# 3xAttenuators.net
KiCad netlist of a schematic drawn in EAGLE
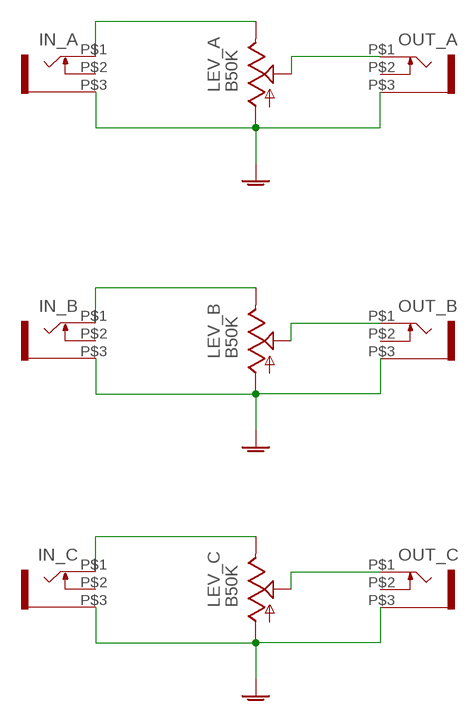
[diagram p0: schematic, sheet 1]

(export (version "E")
  (design (tool "Eeschema 10.0.6"))
  (components
    (comp (ref "IN_A")
      (value "THONKICONN_WQP-PJ301M-12_JACK")
      (footprint "eagle-import:THONKICONN_WQP-PJ301M-12_JACK")
      (libsource (lib "eagle-import") (part "THONKICONN_WQP-PJ301M-12_JACK"))
    )
    (comp (ref "IN_B")
      (value "THONKICONN_WQP-PJ301M-12_JACK")
      (footprint "eagle-import:THONKICONN_WQP-PJ301M-12_JACK")
      (libsource (lib "eagle-import") (part "THONKICONN_WQP-PJ301M-12_JACK"))
    )
    (comp (ref "IN_C")
      (value "THONKICONN_WQP-PJ301M-12_JACK")
      (footprint "eagle-import:THONKICONN_WQP-PJ301M-12_JACK")
      (libsource (lib "eagle-import") (part "THONKICONN_WQP-PJ301M-12_JACK"))
    )
    (comp (ref "LEV_A")
      (value "B50K")
      (footprint "eagle-import:MUSICTHINGMODULAR_9MM_SNAP-IN_POT")
      (libsource (lib "eagle-import") (part "MUSICTHINGMODULAR_9MM_SNAP-IN_POT_"))
    )
    (comp (ref "LEV_B")
      (value "B50K")
      (footprint "eagle-import:MUSICTHINGMODULAR_9MM_SNAP-IN_POT")
      (libsource (lib "eagle-import") (part "MUSICTHINGMODULAR_9MM_SNAP-IN_POT_"))
    )
    (comp (ref "LEV_C")
      (value "B50K")
      (footprint "eagle-import:MUSICTHINGMODULAR_9MM_SNAP-IN_POT")
      (libsource (lib "eagle-import") (part "MUSICTHINGMODULAR_9MM_SNAP-IN_POT_"))
    )
    (comp (ref "OUT_A")
      (value "THONKICONN_WQP-PJ301M-12_JACK")
      (footprint "eagle-import:THONKICONN_WQP-PJ301M-12_JACK")
      (libsource (lib "eagle-import") (part "THONKICONN_WQP-PJ301M-12_JACK"))
    )
    (comp (ref "OUT_B")
      (value "THONKICONN_WQP-PJ301M-12_JACK")
      (footprint "eagle-import:THONKICONN_WQP-PJ301M-12_JACK")
      (libsource (lib "eagle-import") (part "THONKICONN_WQP-PJ301M-12_JACK"))
    )
    (comp (ref "OUT_C")
      (value "THONKICONN_WQP-PJ301M-12_JACK")
      (footprint "eagle-import:THONKICONN_WQP-PJ301M-12_JACK")
      (libsource (lib "eagle-import") (part "THONKICONN_WQP-PJ301M-12_JACK"))
    )
  )
  (nets
    (net (code "1") (name "GNDA") (class "Default")
      (node (ref "IN_A") (pin "P$3") (pinfunction "1_P$3") (pintype "passive"))
      (node (ref "IN_B") (pin "P$3") (pinfunction "1_P$3") (pintype "passive"))
      (node (ref "IN_C") (pin "P$3") (pinfunction "1_P$3") (pintype "passive"))
      (node (ref "LEV_A") (pin "1") (pinfunction "A_1") (pintype "passive"))
      (node (ref "LEV_B") (pin "1") (pinfunction "A_1") (pintype "passive"))
      (node (ref "LEV_C") (pin "1") (pinfunction "A_1") (pintype "passive"))
      (node (ref "OUT_A") (pin "P$3") (pinfunction "1_P$3") (pintype "passive"))
      (node (ref "OUT_B") (pin "P$3") (pinfunction "1_P$3") (pintype "passive"))
      (node (ref "OUT_C") (pin "P$3") (pinfunction "1_P$3") (pintype "passive"))
    )
    (net (code "2") (name "Net-(IN_A-2)") (class "Default")
      (node (ref "IN_A") (pin "P$1") (pinfunction "2_P$1") (pintype "passive"))
      (node (ref "LEV_A") (pin "3") (pinfunction "E_3") (pintype "passive"))
    )
    (net (code "3") (name "Net-(IN_B-2)") (class "Default")
      (node (ref "IN_B") (pin "P$1") (pinfunction "2_P$1") (pintype "passive"))
      (node (ref "LEV_B") (pin "3") (pinfunction "E_3") (pintype "passive"))
    )
    (net (code "4") (name "Net-(IN_C-2)") (class "Default")
      (node (ref "IN_C") (pin "P$1") (pinfunction "2_P$1") (pintype "passive"))
      (node (ref "LEV_C") (pin "3") (pinfunction "E_3") (pintype "passive"))
    )
    (net (code "5") (name "Net-(LEV_A-S)") (class "Default")
      (node (ref "LEV_A") (pin "2") (pinfunction "S_2") (pintype "passive"))
      (node (ref "OUT_A") (pin "P$1") (pinfunction "2_P$1") (pintype "passive"))
    )
    (net (code "6") (name "Net-(LEV_B-S)") (class "Default")
      (node (ref "LEV_B") (pin "2") (pinfunction "S_2") (pintype "passive"))
      (node (ref "OUT_B") (pin "P$1") (pinfunction "2_P$1") (pintype "passive"))
    )
    (net (code "7") (name "Net-(LEV_C-S)") (class "Default")
      (node (ref "LEV_C") (pin "2") (pinfunction "S_2") (pintype "passive"))
      (node (ref "OUT_C") (pin "P$1") (pinfunction "2_P$1") (pintype "passive"))
    )
    (net (code "8") (name "unconnected-(IN_A-3-PadP$2)") (class "Default")
      (node (ref "IN_A") (pin "P$2") (pinfunction "3_P$2") (pintype "passive"))
    )
    (net (code "9") (name "unconnected-(IN_B-3-PadP$2)") (class "Default")
      (node (ref "IN_B") (pin "P$2") (pinfunction "3_P$2") (pintype "passive"))
    )
    (net (code "10") (name "unconnected-(IN_C-3-PadP$2)") (class "Default")
      (node (ref "IN_C") (pin "P$2") (pinfunction "3_P$2") (pintype "passive"))
    )
    (net (code "11") (name "unconnected-(OUT_A-3-PadP$2)") (class "Default")
      (node (ref "OUT_A") (pin "P$2") (pinfunction "3_P$2") (pintype "passive"))
    )
    (net (code "12") (name "unconnected-(OUT_B-3-PadP$2)") (class "Default")
      (node (ref "OUT_B") (pin "P$2") (pinfunction "3_P$2") (pintype "passive"))
    )
    (net (code "13") (name "unconnected-(OUT_C-3-PadP$2)") (class "Default")
      (node (ref "OUT_C") (pin "P$2") (pinfunction "3_P$2") (pintype "passive"))
    )
  )
)
